# TXRobot-Boutons.net
KiCad netlist of a schematic drawn in Altium Designer
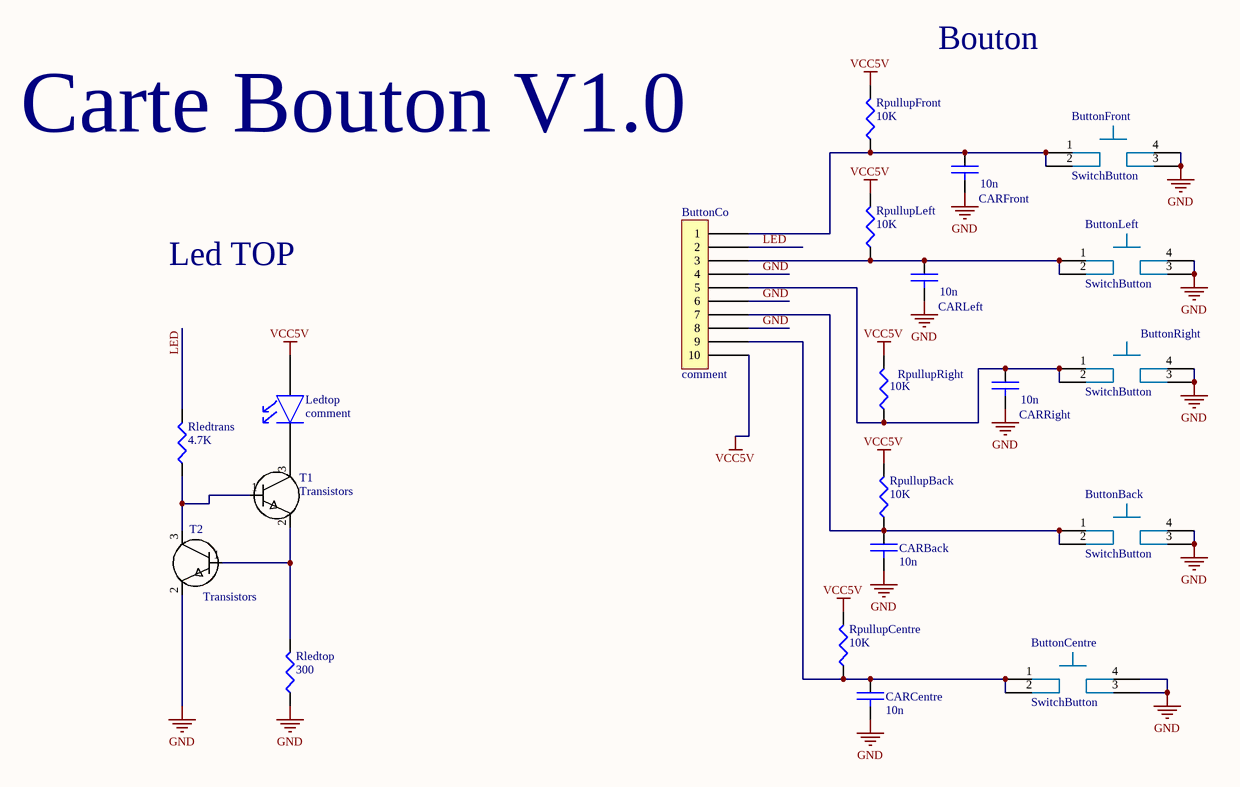
[diagram p0: TXRobot-Boutons.SchDoc]

(export (version "E")
  (design (tool "Eeschema 10.0.6"))
  (components
    (comp (ref "ButtonBack")
      (value "SwitchButton")
      (footprint "SwitchMedium")
      (libsource (lib "SwitchButton") (part "SwitchButton"))
    )
    (comp (ref "ButtonCentre")
      (value "SwitchButton")
      (footprint "SwitchMedium")
      (libsource (lib "SwitchButton") (part "SwitchButton"))
    )
    (comp (ref "ButtonCo")
      (value "comment")
      (footprint "HE10-10V")
      (description "10-pin connector")
      (libsource (lib "ISEN_basics") (part "HE10-10"))
    )
    (comp (ref "ButtonFront")
      (value "SwitchButton")
      (footprint "SwitchMedium")
      (libsource (lib "SwitchButton") (part "SwitchButton"))
    )
    (comp (ref "ButtonLeft")
      (value "SwitchButton")
      (footprint "SwitchMedium")
      (libsource (lib "SwitchButton") (part "SwitchButton"))
    )
    (comp (ref "ButtonRight")
      (value "SwitchButton")
      (footprint "SwitchMedium")
      (libsource (lib "SwitchButton") (part "SwitchButton"))
    )
    (comp (ref "CARBack")
      (value "10n")
      (footprint "0805")
      (description "Capa anti rebond")
      (fields (field (name "Comment") "CAP"))
      (libsource (lib "ISEN_basics") (part "CAP"))
    )
    (comp (ref "CARCentre")
      (value "10n")
      (footprint "0805")
      (description "Capa anti rebond")
      (fields (field (name "Comment") "CAP"))
      (libsource (lib "ISEN_basics") (part "CAP"))
    )
    (comp (ref "CARFront")
      (value "10n")
      (footprint "0805")
      (description "capa Anti rebond")
      (fields (field (name "Comment") "CAP"))
      (libsource (lib "ISEN_basics") (part "CAP"))
    )
    (comp (ref "CARLeft")
      (value "10n")
      (footprint "0805")
      (description "capa Anti rebond")
      (fields (field (name "Comment") "CAP"))
      (libsource (lib "ISEN_basics") (part "CAP"))
    )
    (comp (ref "CARRight")
      (value "10n")
      (footprint "0805")
      (description "capa Anti rebond")
      (fields (field (name "Comment") "CAP"))
      (libsource (lib "ISEN_basics") (part "CAP"))
    )
    (comp (ref "Ledtop")
      (value "comment")
      (footprint "LED1206")
      (description "LED 5mm/3mm/CMS")
      (libsource (lib "ISEN_basics") (part "LED"))
    )
    (comp (ref "Rledtop")
      (value "300")
      (footprint "0805")
      (description "resistance")
      (fields (field (name "Comment") "RES"))
      (libsource (lib "ISEN_basics") (part "RES"))
    )
    (comp (ref "Rledtrans")
      (value "4.7K")
      (footprint "0805")
      (description "resistance")
      (fields (field (name "Comment") "RES"))
      (libsource (lib "ISEN_basics") (part "RES"))
    )
    (comp (ref "RpullupBack")
      (value "10K")
      (footprint "0805")
      (description "resistance")
      (fields (field (name "Comment") "RES"))
      (libsource (lib "ISEN_basics") (part "RES"))
    )
    (comp (ref "RpullupCentre")
      (value "10K")
      (footprint "0805")
      (description "resistance")
      (fields (field (name "Comment") "RES"))
      (libsource (lib "ISEN_basics") (part "RES"))
    )
    (comp (ref "RpullupFront")
      (value "10K")
      (footprint "0805")
      (description "resistance")
      (fields (field (name "Comment") "RES"))
      (libsource (lib "ISEN_basics") (part "RES"))
    )
    (comp (ref "RpullupLeft")
      (value "10K")
      (footprint "0805")
      (description "resistance")
      (fields (field (name "Comment") "RES"))
      (libsource (lib "ISEN_basics") (part "RES"))
    )
    (comp (ref "RpullupRight")
      (value "10K")
      (footprint "0805")
      (description "resistance")
      (fields (field (name "Comment") "RES"))
      (libsource (lib "ISEN_basics") (part "RES"))
    )
    (comp (ref "T1") (value "Transistors") (footprint "BC817-40") (libsource (lib "") (part "Transistors_1")))
    (comp (ref "T2")
      (value "Transistors")
      (footprint "BC817-40")
      (libsource (lib "Transistors") (part "Transistors"))
    )
  )
  (nets
    (net (code "1") (name "/LED") (class "Default")
      (node (ref "ButtonCo") (pin "2") (pinfunction "2_2") (pintype "passive"))
      (node (ref "Rledtrans") (pin "2") (pintype "passive"))
    )
    (net (code "2") (name "GND") (class "Default")
      (node (ref "ButtonBack") (pin "3") (pinfunction "3_3") (pintype "passive"))
      (node (ref "ButtonBack") (pin "4") (pinfunction "4_4") (pintype "passive"))
      (node (ref "ButtonCentre") (pin "3") (pinfunction "3_3") (pintype "passive"))
      (node (ref "ButtonCentre") (pin "4") (pinfunction "4_4") (pintype "passive"))
      (node (ref "ButtonCo") (pin "4") (pinfunction "4_4") (pintype "passive"))
      (node (ref "ButtonCo") (pin "6") (pinfunction "6_6") (pintype "passive"))
      (node (ref "ButtonCo") (pin "8") (pinfunction "8_8") (pintype "passive"))
      (node (ref "ButtonFront") (pin "3") (pinfunction "3_3") (pintype "passive"))
      (node (ref "ButtonFront") (pin "4") (pinfunction "4_4") (pintype "passive"))
      (node (ref "ButtonLeft") (pin "3") (pinfunction "3_3") (pintype "passive"))
      (node (ref "ButtonLeft") (pin "4") (pinfunction "4_4") (pintype "passive"))
      (node (ref "ButtonRight") (pin "3") (pinfunction "3_3") (pintype "passive"))
      (node (ref "ButtonRight") (pin "4") (pinfunction "4_4") (pintype "passive"))
      (node (ref "CARBack") (pin "2") (pinfunction "2_2") (pintype "passive"))
      (node (ref "CARCentre") (pin "2") (pinfunction "2_2") (pintype "passive"))
      (node (ref "CARFront") (pin "2") (pinfunction "2_2") (pintype "passive"))
      (node (ref "CARLeft") (pin "2") (pinfunction "2_2") (pintype "passive"))
      (node (ref "CARRight") (pin "2") (pinfunction "2_2") (pintype "passive"))
      (node (ref "Rledtop") (pin "1") (pintype "passive"))
      (node (ref "T2") (pin "2") (pinfunction "Emi_2") (pintype "passive"))
    )
    (net (code "3") (name "Net-(ButtonBack-Pad1)") (class "Default")
      (node (ref "ButtonBack") (pin "1") (pinfunction "1_1") (pintype "passive"))
      (node (ref "ButtonBack") (pin "2") (pinfunction "2_2") (pintype "passive"))
      (node (ref "ButtonCo") (pin "7") (pinfunction "7_7") (pintype "passive"))
      (node (ref "CARBack") (pin "1") (pinfunction "1_1") (pintype "passive"))
      (node (ref "RpullupBack") (pin "1") (pintype "passive"))
    )
    (net (code "4") (name "Net-(ButtonCentre-Pad1)") (class "Default")
      (node (ref "ButtonCentre") (pin "1") (pinfunction "1_1") (pintype "passive"))
      (node (ref "ButtonCentre") (pin "2") (pinfunction "2_2") (pintype "passive"))
      (node (ref "ButtonCo") (pin "9") (pinfunction "9_9") (pintype "passive"))
      (node (ref "CARCentre") (pin "1") (pinfunction "1_1") (pintype "passive"))
      (node (ref "RpullupCentre") (pin "1") (pintype "passive"))
    )
    (net (code "5") (name "Net-(ButtonCo-Pad1)") (class "Default")
      (node (ref "ButtonCo") (pin "1") (pinfunction "1_1") (pintype "passive"))
      (node (ref "ButtonFront") (pin "1") (pinfunction "1_1") (pintype "passive"))
      (node (ref "ButtonFront") (pin "2") (pinfunction "2_2") (pintype "passive"))
      (node (ref "CARFront") (pin "1") (pinfunction "1_1") (pintype "passive"))
      (node (ref "RpullupFront") (pin "1") (pintype "passive"))
    )
    (net (code "6") (name "Net-(ButtonCo-Pad3)") (class "Default")
      (node (ref "ButtonCo") (pin "3") (pinfunction "3_3") (pintype "passive"))
      (node (ref "ButtonLeft") (pin "1") (pinfunction "1_1") (pintype "passive"))
      (node (ref "ButtonLeft") (pin "2") (pinfunction "2_2") (pintype "passive"))
      (node (ref "CARLeft") (pin "1") (pinfunction "1_1") (pintype "passive"))
      (node (ref "RpullupLeft") (pin "1") (pintype "passive"))
    )
    (net (code "7") (name "Net-(ButtonCo-Pad5)") (class "Default")
      (node (ref "ButtonCo") (pin "5") (pinfunction "5_5") (pintype "passive"))
      (node (ref "ButtonRight") (pin "1") (pinfunction "1_1") (pintype "passive"))
      (node (ref "ButtonRight") (pin "2") (pinfunction "2_2") (pintype "passive"))
      (node (ref "CARRight") (pin "1") (pinfunction "1_1") (pintype "passive"))
      (node (ref "RpullupRight") (pin "1") (pintype "passive"))
    )
    (net (code "8") (name "Net-(Ledtop-10)") (class "Default")
      (node (ref "Ledtop") (pin "K") (pinfunction "10_K") (pintype "passive"))
      (node (ref "T1") (pin "3") (pinfunction "Co_3") (pintype "passive"))
    )
    (net (code "9") (name "Net-(T1-Base)") (class "Default")
      (node (ref "Rledtrans") (pin "1") (pintype "passive"))
      (node (ref "T1") (pin "1") (pinfunction "Base_1") (pintype "passive"))
      (node (ref "T2") (pin "3") (pinfunction "Co_3") (pintype "passive"))
    )
    (net (code "10") (name "Net-(T1-Emi)") (class "Default")
      (node (ref "Rledtop") (pin "2") (pintype "passive"))
      (node (ref "T1") (pin "2") (pinfunction "Emi_2") (pintype "passive"))
      (node (ref "T2") (pin "1") (pinfunction "Base_1") (pintype "passive"))
    )
    (net (code "11") (name "VCC5V") (class "Default")
      (node (ref "ButtonCo") (pin "10") (pinfunction "10_10") (pintype "passive"))
      (node (ref "Ledtop") (pin "A") (pinfunction "8_A") (pintype "passive"))
      (node (ref "RpullupBack") (pin "2") (pintype "passive"))
      (node (ref "RpullupCentre") (pin "2") (pintype "passive"))
      (node (ref "RpullupFront") (pin "2") (pintype "passive"))
      (node (ref "RpullupLeft") (pin "2") (pintype "passive"))
      (node (ref "RpullupRight") (pin "2") (pintype "passive"))
    )
  )
)
